# G624X.net
KiCad netlist of a schematic drawn in EAGLE
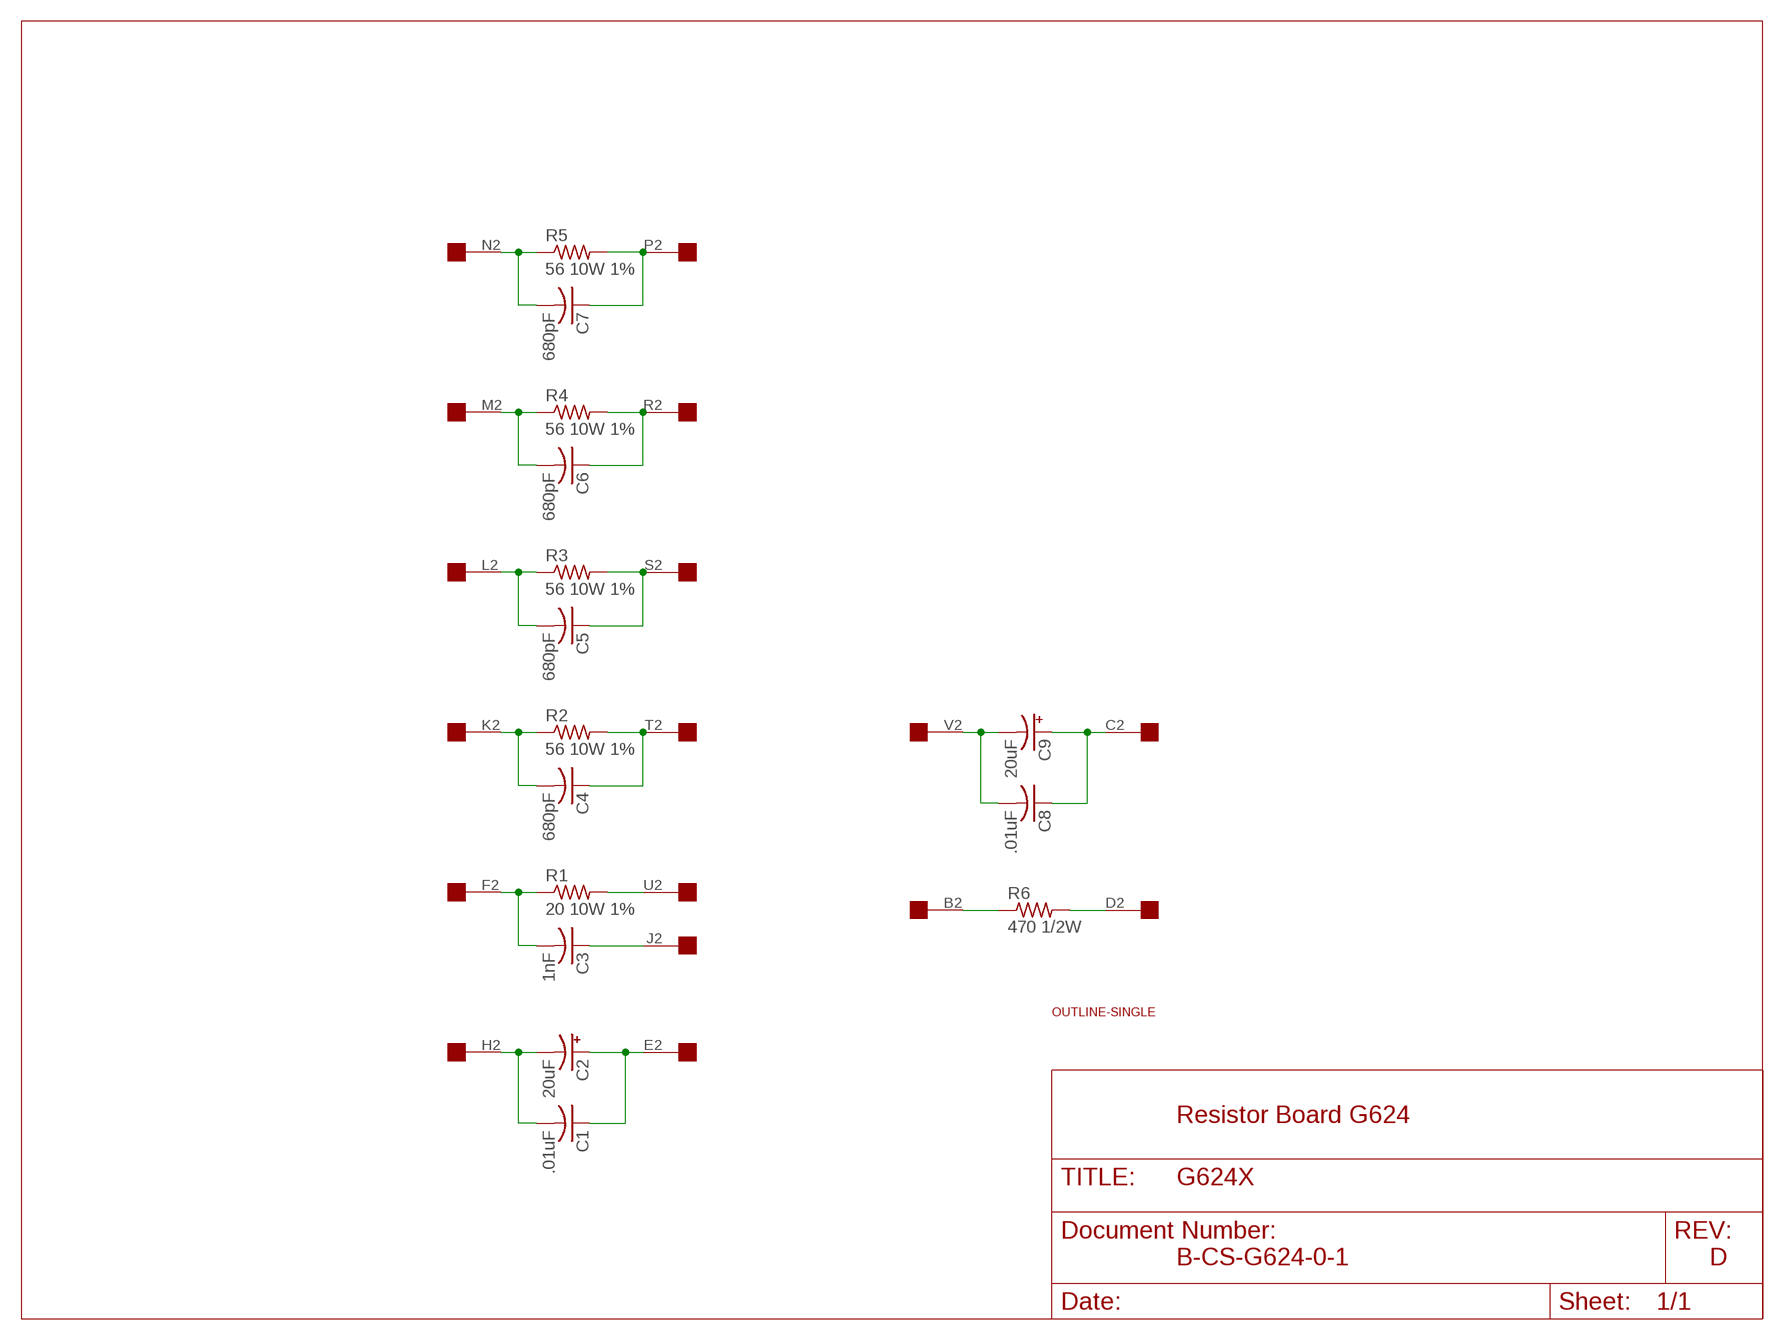
[diagram p0: schematic, sheet 1]

(export (version "E")
  (design (tool "Eeschema 10.0.6"))
  (components
    (comp (ref "C1")
      (value ".01uF")
      (footprint "eagle-import:C050-025X075")
      (libsource (lib "eagle-import") (part "C-US050-025X075"))
    )
    (comp (ref "C2")
      (value "20uF")
      (footprint "eagle-import:E28-8")
      (libsource (lib "eagle-import") (part "CPOL-USE28-8AXIAL"))
    )
    (comp (ref "C3")
      (value "1nF")
      (footprint "eagle-import:C050-025X075")
      (libsource (lib "eagle-import") (part "C-US050-025X075"))
    )
    (comp (ref "C4")
      (value "680pF")
      (footprint "eagle-import:C150-054X183")
      (libsource (lib "eagle-import") (part "C-US150-054X183"))
    )
    (comp (ref "C5")
      (value "680pF")
      (footprint "eagle-import:C150-054X183")
      (libsource (lib "eagle-import") (part "C-US150-054X183"))
    )
    (comp (ref "C6")
      (value "680pF")
      (footprint "eagle-import:C050-025X075")
      (libsource (lib "eagle-import") (part "C-US050-025X075"))
    )
    (comp (ref "C7")
      (value "680pF")
      (footprint "eagle-import:C050-025X075")
      (libsource (lib "eagle-import") (part "C-US050-025X075"))
    )
    (comp (ref "C8")
      (value ".01uF")
      (footprint "eagle-import:C050-025X075")
      (libsource (lib "eagle-import") (part "C-US050-025X075"))
    )
    (comp (ref "C9")
      (value "20uF")
      (footprint "eagle-import:E28-8")
      (libsource (lib "eagle-import") (part "CPOL-USE28-8AXIAL"))
    )
    (comp (ref "R1")
      (value "20 10W 1%")
      (footprint "eagle-import:0944_51")
      (libsource (lib "eagle-import") (part "R-US_0944/51"))
    )
    (comp (ref "R2")
      (value "56 10W 1%")
      (footprint "eagle-import:0944_51")
      (libsource (lib "eagle-import") (part "R-US_0944/51"))
    )
    (comp (ref "R3")
      (value "56 10W 1%")
      (footprint "eagle-import:0944_51")
      (libsource (lib "eagle-import") (part "R-US_0944/51"))
    )
    (comp (ref "R4")
      (value "56 10W 1%")
      (footprint "eagle-import:0944_51")
      (libsource (lib "eagle-import") (part "R-US_0944/51"))
    )
    (comp (ref "R5")
      (value "56 10W 1%")
      (footprint "eagle-import:0944_51")
      (libsource (lib "eagle-import") (part "R-US_0944/51"))
    )
    (comp (ref "R6")
      (value "470 1/2W")
      (footprint "eagle-import:0411_15")
      (libsource (lib "eagle-import") (part "R-US_0411/15"))
    )
    (comp (ref "U$1")
      (value "EDGE-1")
      (footprint "eagle-import:EDGE-CON1")
      (libsource (lib "eagle-import") (part "EDGE-1"))
    )
    (comp (ref "U$2")
      (value "OUTLINE-SINGLE")
      (footprint "eagle-import:SINGLE")
      (libsource (lib "eagle-import") (part "OUTLINE-SINGLE"))
    )
  )
  (nets
    (net (code "1") (name "Net-(U$1B-1)") (class "Default")
      (node (ref "R6") (pin "1") (pinfunction "1_1") (pintype "passive"))
      (node (ref "U$1") (pin "B2") (pinfunction "1_B2") (pintype "bidirectional"))
    )
    (net (code "2") (name "Net-(U$1C-1)") (class "Default")
      (node (ref "C8") (pin "1") (pinfunction "1_1") (pintype "passive"))
      (node (ref "C9") (pin "+") (pinfunction "+_+") (pintype "passive"))
      (node (ref "U$1") (pin "C2") (pinfunction "1_C2") (pintype "bidirectional"))
    )
    (net (code "3") (name "Net-(U$1D-1)") (class "Default")
      (node (ref "R6") (pin "2") (pinfunction "2_2") (pintype "passive"))
      (node (ref "U$1") (pin "D2") (pinfunction "1_D2") (pintype "bidirectional"))
    )
    (net (code "4") (name "Net-(U$1E-1)") (class "Default")
      (node (ref "C1") (pin "1") (pinfunction "1_1") (pintype "passive"))
      (node (ref "C2") (pin "+") (pinfunction "+_+") (pintype "passive"))
      (node (ref "U$1") (pin "E2") (pinfunction "1_E2") (pintype "bidirectional"))
    )
    (net (code "5") (name "Net-(U$1F-1)") (class "Default")
      (node (ref "C3") (pin "2") (pinfunction "2_2") (pintype "passive"))
      (node (ref "R1") (pin "1") (pinfunction "1_1") (pintype "passive"))
      (node (ref "U$1") (pin "F2") (pinfunction "1_F2") (pintype "bidirectional"))
    )
    (net (code "6") (name "Net-(U$1G-1)") (class "Default")
      (node (ref "C1") (pin "2") (pinfunction "2_2") (pintype "passive"))
      (node (ref "C2") (pin "-") (pinfunction "-_-") (pintype "passive"))
      (node (ref "U$1") (pin "H2") (pinfunction "1_H2") (pintype "bidirectional"))
    )
    (net (code "7") (name "Net-(U$1H-1)") (class "Default")
      (node (ref "C3") (pin "1") (pinfunction "1_1") (pintype "passive"))
      (node (ref "U$1") (pin "J2") (pinfunction "1_J2") (pintype "bidirectional"))
    )
    (net (code "8") (name "Net-(U$1I-1)") (class "Default")
      (node (ref "C4") (pin "2") (pinfunction "2_2") (pintype "passive"))
      (node (ref "R2") (pin "1") (pinfunction "1_1") (pintype "passive"))
      (node (ref "U$1") (pin "K2") (pinfunction "1_K2") (pintype "bidirectional"))
    )
    (net (code "9") (name "Net-(U$1J-1)") (class "Default")
      (node (ref "C5") (pin "2") (pinfunction "2_2") (pintype "passive"))
      (node (ref "R3") (pin "1") (pinfunction "1_1") (pintype "passive"))
      (node (ref "U$1") (pin "L2") (pinfunction "1_L2") (pintype "bidirectional"))
    )
    (net (code "10") (name "Net-(U$1K-1)") (class "Default")
      (node (ref "C6") (pin "2") (pinfunction "2_2") (pintype "passive"))
      (node (ref "R4") (pin "1") (pinfunction "1_1") (pintype "passive"))
      (node (ref "U$1") (pin "M2") (pinfunction "1_M2") (pintype "bidirectional"))
    )
    (net (code "11") (name "Net-(U$1L-1)") (class "Default")
      (node (ref "C7") (pin "2") (pinfunction "2_2") (pintype "passive"))
      (node (ref "R5") (pin "1") (pinfunction "1_1") (pintype "passive"))
      (node (ref "U$1") (pin "N2") (pinfunction "1_N2") (pintype "bidirectional"))
    )
    (net (code "12") (name "Net-(U$1M-1)") (class "Default")
      (node (ref "C7") (pin "1") (pinfunction "1_1") (pintype "passive"))
      (node (ref "R5") (pin "2") (pinfunction "2_2") (pintype "passive"))
      (node (ref "U$1") (pin "P2") (pinfunction "1_P2") (pintype "bidirectional"))
    )
    (net (code "13") (name "Net-(U$1N-1)") (class "Default")
      (node (ref "C6") (pin "1") (pinfunction "1_1") (pintype "passive"))
      (node (ref "R4") (pin "2") (pinfunction "2_2") (pintype "passive"))
      (node (ref "U$1") (pin "R2") (pinfunction "1_R2") (pintype "bidirectional"))
    )
    (net (code "14") (name "Net-(U$1O-1)") (class "Default")
      (node (ref "C5") (pin "1") (pinfunction "1_1") (pintype "passive"))
      (node (ref "R3") (pin "2") (pinfunction "2_2") (pintype "passive"))
      (node (ref "U$1") (pin "S2") (pinfunction "1_S2") (pintype "bidirectional"))
    )
    (net (code "15") (name "Net-(U$1P-1)") (class "Default")
      (node (ref "C4") (pin "1") (pinfunction "1_1") (pintype "passive"))
      (node (ref "R2") (pin "2") (pinfunction "2_2") (pintype "passive"))
      (node (ref "U$1") (pin "T2") (pinfunction "1_T2") (pintype "bidirectional"))
    )
    (net (code "16") (name "Net-(U$1Q-1)") (class "Default")
      (node (ref "R1") (pin "2") (pinfunction "2_2") (pintype "passive"))
      (node (ref "U$1") (pin "U2") (pinfunction "1_U2") (pintype "bidirectional"))
    )
    (net (code "17") (name "Net-(U$1R-1)") (class "Default")
      (node (ref "C8") (pin "2") (pinfunction "2_2") (pintype "passive"))
      (node (ref "C9") (pin "-") (pinfunction "-_-") (pintype "passive"))
      (node (ref "U$1") (pin "V2") (pinfunction "1_V2") (pintype "bidirectional"))
    )
  )
)
